# UARTtoRS485.net
KiCad netlist of a schematic drawn in Altium Designer
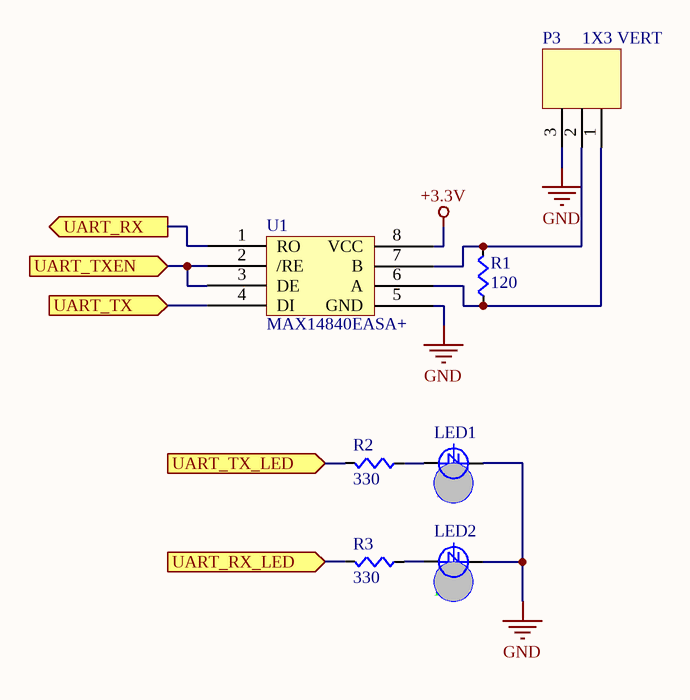
[diagram p0: UARTtoRS485.SchDoc]

(export (version "E")
  (design (tool "Eeschema 10.0.6"))
  (components
    (comp (ref "LED1")
      (value "LED")
      (footprint "LED0603")
      (description "LED RED CLEAR 0603 SMD")
      (fields (field (name "COLOR") "TX"))
      (libsource (lib "Semiconductors") (part "LED"))
    )
    (comp (ref "LED2")
      (value "LED")
      (footprint "LED0603")
      (description "LED GREEN CLEAR 0603 SMD")
      (fields (field (name "COLOR") "RX"))
      (libsource (lib "Semiconductors") (part "LED"))
    )
    (comp (ref "P3")
      (value "1X3 VERT")
      (footprint "MOLEX-HDR-1X3-SHERLOCK-VERT")
      (description "CONN HEADER 3POS 2MM VERT TIN")
      (libsource (lib "Connectors") (part "MOLEX-HDR-1x3-SHERLOCK_VERT"))
    )
    (comp (ref "R1")
      (value "120")
      (footprint "RES0603")
      (description "RES SMD 120 OHM 1% 1/10W 0603")
      (fields (field (name "Comment") "Res"))
      (libsource (lib "Passives") (part "Res"))
    )
    (comp (ref "R2")
      (value "330")
      (footprint "RES0603")
      (description "RES SMD 330 OHM 1% 1/10W 0603")
      (fields (field (name "Comment") "Res"))
      (libsource (lib "Passives") (part "Res"))
    )
    (comp (ref "R3")
      (value "330")
      (footprint "RES0603")
      (description "RES SMD 330 OHM 1% 1/10W 0603")
      (fields (field (name "Comment") "Res"))
      (libsource (lib "Passives") (part "Res"))
    )
    (comp (ref "U1")
      (value "MAX14840EASA+")
      (footprint "MAX14840EASA+")
      (description "IC TXRX RS422/485 40MBPS 8SOIC")
      (libsource (lib "ICs") (part "MAX14840EASA+"))
    )
  )
  (nets
    (net (code "1") (name "+3.3V") (class "Default")
      (node (ref "U1") (pin "8") (pinfunction "VCC_8") (pintype "passive"))
    )
    (net (code "2") (name "/UART_RX") (class "Default")
      (node (ref "U1") (pin "1") (pinfunction "RO_1") (pintype "passive"))
    )
    (net (code "3") (name "/UART_RX_LED") (class "Default")
      (node (ref "R3") (pin "1") (pinfunction "A_1") (pintype "passive"))
    )
    (net (code "4") (name "/UART_TX") (class "Default")
      (node (ref "U1") (pin "4") (pinfunction "DI_4") (pintype "passive"))
    )
    (net (code "5") (name "/UART_TXEN") (class "Default")
      (node (ref "U1") (pin "2") (pinfunction "/RE_2") (pintype "passive"))
      (node (ref "U1") (pin "3") (pinfunction "DE_3") (pintype "passive"))
    )
    (net (code "6") (name "/UART_TX_LED") (class "Default")
      (node (ref "R2") (pin "1") (pinfunction "A_1") (pintype "passive"))
    )
    (net (code "7") (name "GND") (class "Default")
      (node (ref "LED1") (pin "C") (pinfunction "C_C") (pintype "passive"))
      (node (ref "LED2") (pin "C") (pinfunction "C_C") (pintype "passive"))
      (node (ref "P3") (pin "3") (pinfunction "3_3") (pintype "passive"))
      (node (ref "U1") (pin "5") (pinfunction "GND_5") (pintype "passive"))
    )
    (net (code "8") (name "Net-(R1-A)") (class "Default")
      (node (ref "P3") (pin "2") (pinfunction "2_2") (pintype "passive"))
      (node (ref "R1") (pin "1") (pinfunction "A_1") (pintype "passive"))
      (node (ref "U1") (pin "7") (pinfunction "B_7") (pintype "passive"))
    )
    (net (code "9") (name "Net-(R1-B)") (class "Default")
      (node (ref "P3") (pin "1") (pinfunction "1_1") (pintype "passive"))
      (node (ref "R1") (pin "2") (pinfunction "B_2") (pintype "passive"))
      (node (ref "U1") (pin "6") (pinfunction "A_6") (pintype "passive"))
    )
    (net (code "10") (name "Net-(R2-B)") (class "Default")
      (node (ref "LED1") (pin "A") (pinfunction "A_A") (pintype "passive"))
      (node (ref "R2") (pin "2") (pinfunction "B_2") (pintype "passive"))
    )
    (net (code "11") (name "Net-(R3-B)") (class "Default")
      (node (ref "LED2") (pin "A") (pinfunction "A_A") (pintype "passive"))
      (node (ref "R3") (pin "2") (pinfunction "B_2") (pintype "passive"))
    )
  )
)
